# Connectors.net
KiCad netlist of a schematic drawn in Altium Designer
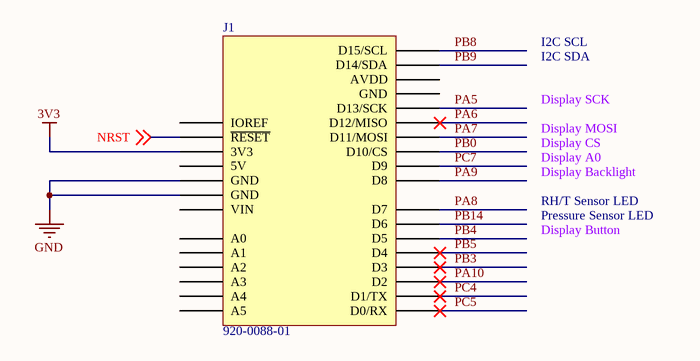
[diagram p0: Connectors.SchDoc]

(export (version "E")
  (design (tool "Eeschema 10.0.6"))
  (components
    (comp (ref "J1")
      (value "920-0088-01")
      (footprint "SCHMARTBOARD - 920-0088-01")
      (description "CONN HDR 8/10P 0.1 GOLD PCB 6PC")
      (fields (field (name "MANUFACTURER") "Schmartboard, Inc."))
      (libsource (lib "altiumlibrary.com") (part "Arduino Headers"))
    )
  )
  (nets
    (net (code "1") (name "/PA5") (class "Default")
      (node (ref "J1") (pin "28") (pinfunction "D13/SCK_28") (pintype "passive"))
    )
    (net (code "2") (name "/PA6") (class "Default")
      (node (ref "J1") (pin "27") (pinfunction "D12/MISO_27") (pintype "passive+no_connect"))
    )
    (net (code "3") (name "/PA7") (class "Default")
      (node (ref "J1") (pin "26") (pinfunction "D11/MOSI_26") (pintype "passive"))
    )
    (net (code "4") (name "/PA8") (class "Default")
      (node (ref "J1") (pin "22") (pinfunction "D7_22") (pintype "passive"))
    )
    (net (code "5") (name "/PA9") (class "Default")
      (node (ref "J1") (pin "23") (pinfunction "D8_23") (pintype "passive"))
    )
    (net (code "6") (name "/PA10") (class "Default")
      (node (ref "J1") (pin "17") (pinfunction "D2_17") (pintype "passive+no_connect"))
    )
    (net (code "7") (name "/PB0") (class "Default")
      (node (ref "J1") (pin "25") (pinfunction "D10/CS_25") (pintype "passive"))
    )
    (net (code "8") (name "/PB3") (class "Default")
      (node (ref "J1") (pin "18") (pinfunction "D3_18") (pintype "passive+no_connect"))
    )
    (net (code "9") (name "/PB4") (class "Default")
      (node (ref "J1") (pin "20") (pinfunction "D5_20") (pintype "passive"))
    )
    (net (code "10") (name "/PB5") (class "Default")
      (node (ref "J1") (pin "19") (pinfunction "D4_19") (pintype "passive+no_connect"))
    )
    (net (code "11") (name "/PB8") (class "Default")
      (node (ref "J1") (pin "32") (pinfunction "D15/SCL_32") (pintype "passive"))
    )
    (net (code "12") (name "/PB9") (class "Default")
      (node (ref "J1") (pin "31") (pinfunction "D14/SDA_31") (pintype "passive"))
    )
    (net (code "13") (name "/PB14") (class "Default")
      (node (ref "J1") (pin "21") (pinfunction "D6_21") (pintype "passive"))
    )
    (net (code "14") (name "/PC4") (class "Default")
      (node (ref "J1") (pin "16") (pinfunction "D1/TX_16") (pintype "passive+no_connect"))
    )
    (net (code "15") (name "/PC5") (class "Default")
      (node (ref "J1") (pin "15") (pinfunction "D0/RX_15") (pintype "passive+no_connect"))
    )
    (net (code "16") (name "/PC7") (class "Default")
      (node (ref "J1") (pin "24") (pinfunction "D9_24") (pintype "passive"))
    )
    (net (code "17") (name "3V3") (class "Default")
      (node (ref "J1") (pin "4") (pinfunction "3V3_4") (pintype "passive"))
    )
    (net (code "18") (name "GND") (class "Default")
      (node (ref "J1") (pin "6") (pinfunction "GND_6") (pintype "passive"))
      (node (ref "J1") (pin "7") (pinfunction "GND_7") (pintype "passive"))
    )
    (net (code "19") (name "NRST") (class "Default")
      (node (ref "J1") (pin "3") (pinfunction "~{RESET}_3") (pintype "passive"))
    )
    (net (code "20") (name "unconnected-(J1-5V-Pad5)") (class "Default")
      (node (ref "J1") (pin "5") (pinfunction "5V_5") (pintype "passive"))
    )
    (net (code "21") (name "unconnected-(J1-A0-Pad9)") (class "Default")
      (node (ref "J1") (pin "9") (pinfunction "A0_9") (pintype "passive"))
    )
    (net (code "22") (name "unconnected-(J1-A1-Pad10)") (class "Default")
      (node (ref "J1") (pin "10") (pinfunction "A1_10") (pintype "passive"))
    )
    (net (code "23") (name "unconnected-(J1-A2-Pad11)") (class "Default")
      (node (ref "J1") (pin "11") (pinfunction "A2_11") (pintype "passive"))
    )
    (net (code "24") (name "unconnected-(J1-A3-Pad12)") (class "Default")
      (node (ref "J1") (pin "12") (pinfunction "A3_12") (pintype "passive"))
    )
    (net (code "25") (name "unconnected-(J1-A4-Pad13)") (class "Default")
      (node (ref "J1") (pin "13") (pinfunction "A4_13") (pintype "passive"))
    )
    (net (code "26") (name "unconnected-(J1-A5-Pad14)") (class "Default")
      (node (ref "J1") (pin "14") (pinfunction "A5_14") (pintype "passive"))
    )
    (net (code "27") (name "unconnected-(J1-AVDD-Pad30)") (class "Default")
      (node (ref "J1") (pin "30") (pinfunction "AVDD_30") (pintype "passive"))
    )
    (net (code "28") (name "unconnected-(J1-GND-Pad29)") (class "Default")
      (node (ref "J1") (pin "29") (pinfunction "GND_29") (pintype "passive"))
    )
    (net (code "29") (name "unconnected-(J1-IOREF-Pad2)") (class "Default")
      (node (ref "J1") (pin "2") (pinfunction "IOREF_2") (pintype "passive"))
    )
    (net (code "30") (name "unconnected-(J1-VIN-Pad8)") (class "Default")
      (node (ref "J1") (pin "8") (pinfunction "VIN_8") (pintype "passive"))
    )
  )
)
